# Sheet1.net
KiCad netlist of a schematic drawn in Altium Designer
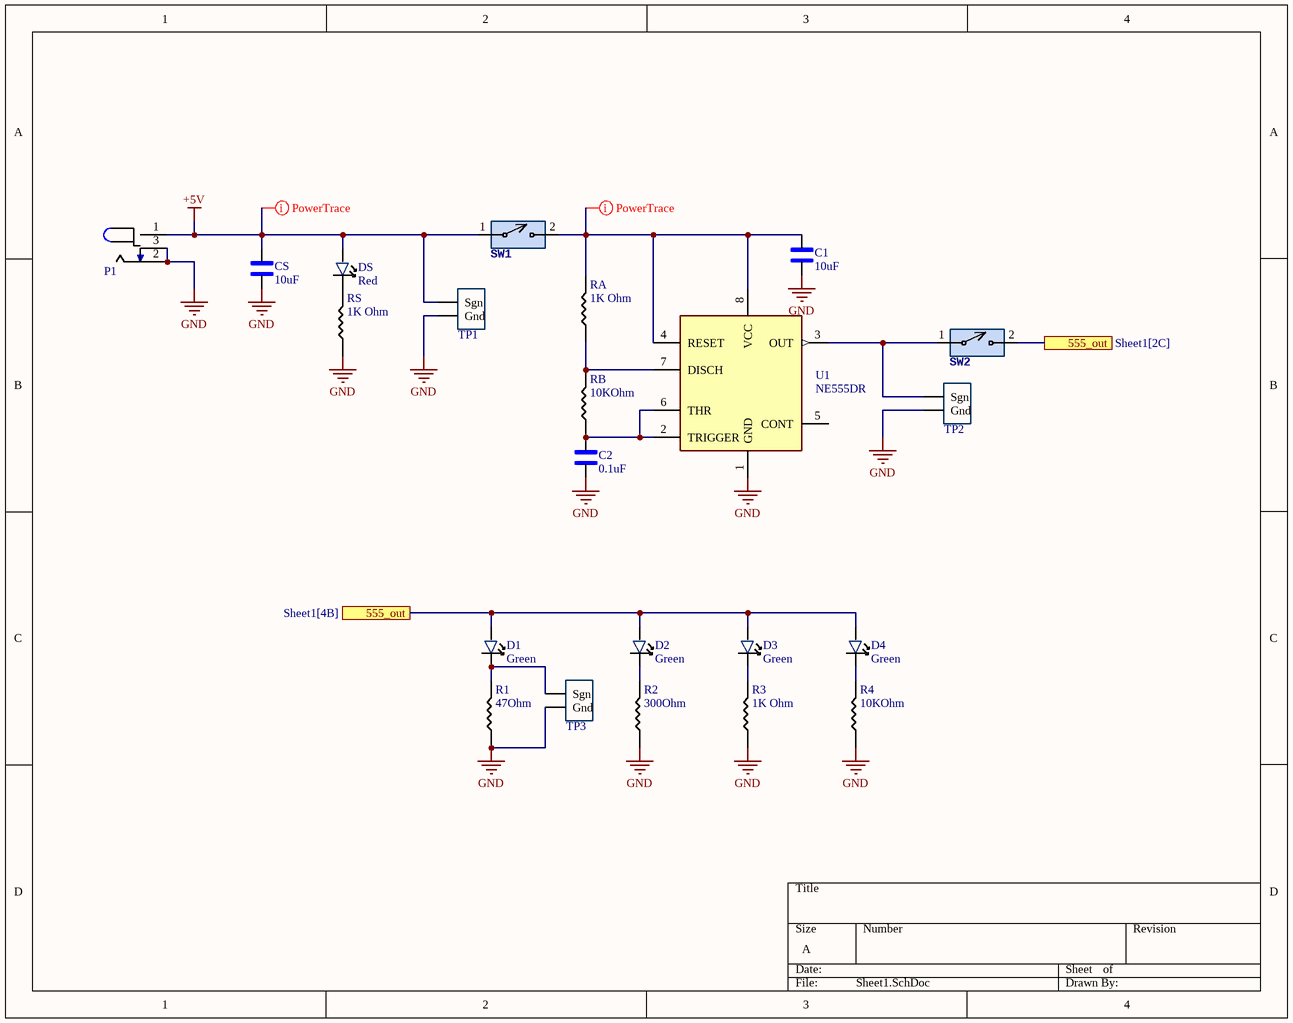
[diagram p0: Sheet1.SchDoc]

(export (version "E")
  (design (tool "Eeschema 10.0.6"))
  (components
    (comp (ref "C1")
      (value "10uF")
      (footprint "1206_Passive_Capacitor")
      (description "10uF ±10% 50V X5R 1206 Multilayer Ceramic Capacitors MLCC - SMD/SMT RoHS")
      (fields (field (name "LCSC PART#") "C13585") (field (name "MFR PART #") "CL31A106KBHNNNE"))
      (libsource (lib "ECEN5730Lib") (part "C_10uF_1206"))
    )
    (comp (ref "C2")
      (value "0.1uF")
      (footprint "1206_Passive_Capacitor")
      (description "MULTILAYER CERAMIC CAPACITORS MLCC - SMD/SMT 1UF 50V 1206 ROHS")
      (fields (field (name "MFR PART #") "CL31B105KBHNNNE") (field (name "LCSC PART#") "C1848"))
      (libsource (lib "ECEN5730Lib") (part "C_1uF_1206"))
    )
    (comp (ref "CS")
      (value "10uF")
      (footprint "1206_Passive_Capacitor")
      (description "10uF ±10% 50V X5R 1206 Multilayer Ceramic Capacitors MLCC - SMD/SMT RoHS")
      (fields (field (name "LCSC PART#") "C13585") (field (name "MFR PART #") "CL31A106KBHNNNE"))
      (libsource (lib "ECEN5730Lib") (part "C_10uF_1206"))
    )
    (comp (ref "D1")
      (value "Green")
      (footprint "LED_1206")
      (description "Green 513~528nm 1206 Light Emitting Diodes (LED) RoHS")
      (fields (field (name "MFR PART #") "SZYY1206G") (field (name "LCSC PART#") "C434439"))
      (libsource (lib "ECEN5730Lib") (part "LED_GREEN_1206"))
    )
    (comp (ref "D2")
      (value "Green")
      (footprint "LED_1206")
      (description "Green 513~528nm 1206 Light Emitting Diodes (LED) RoHS")
      (fields (field (name "MFR PART #") "SZYY1206G") (field (name "LCSC PART#") "C434439"))
      (libsource (lib "ECEN5730Lib") (part "LED_GREEN_1206"))
    )
    (comp (ref "D3")
      (value "Green")
      (footprint "LED_1206")
      (description "Green 513~528nm 1206 Light Emitting Diodes (LED) RoHS")
      (fields (field (name "MFR PART #") "SZYY1206G") (field (name "LCSC PART#") "C434439"))
      (libsource (lib "ECEN5730Lib") (part "LED_GREEN_1206"))
    )
    (comp (ref "D4")
      (value "Green")
      (footprint "LED_1206")
      (description "Green 513~528nm 1206 Light Emitting Diodes (LED) RoHS")
      (fields (field (name "MFR PART #") "SZYY1206G") (field (name "LCSC PART#") "C434439"))
      (libsource (lib "ECEN5730Lib") (part "LED_GREEN_1206"))
    )
    (comp (ref "DS")
      (value "Red")
      (footprint "LED_1206")
      (description "Red 621~631nm 1206 Light Emitting Diodes (LED) RoHS")
      (fields (field (name "MFR PART #") "15-21/R6C-FQ1R1B/2T") (field (name "LCSC PART#") "C93133"))
      (libsource (lib "ECEN5730Lib") (part "LED_RED_1206"))
    )
    (comp (ref "P1")
      (value "Power Jack")
      (footprint "Power_Jack")
      (description "Power Barrel Connector Jack 2.10mm ID (0.083\"), 5.50mm OD (0.217\") Through Hole, Right Angle")
      (fields (field (name "MFR PART #") "PJ-102A") (field (name "LCSC PART#") "C136744"))
      (libsource (lib "ECEN5730Lib") (part "P_Power Jack"))
    )
    (comp (ref "R1")
      (value "47Ohm")
      (footprint "1206_Passive_Resitor")
      (description "47Ω ±5% 0.25W ±200ppm/℃ 1206 Chip Resistor - Surface Mount RoHS")
      (fields (field (name "MFR PART #") "1206W4J0470T5E") (field (name "LCSC PART#") "C25384"))
      (libsource (lib "ECEN5730Lib") (part "R_47Ohm_1206"))
    )
    (comp (ref "R2")
      (value "300Ohm")
      (footprint "1206_Passive_Resitor")
      (description "CHIP RESISTOR - SURFACE MOUNT 300OHMS ±1% 1/4W 1206 ROHS")
      (fields (field (name "MFR PART #") "1206W4F3000T5E") (field (name "LCSC PART#") "C17887"))
      (libsource (lib "ECEN5730Lib") (part "R_300Ohm_1206"))
    )
    (comp (ref "R3")
      (value "1K Ohm")
      (footprint "1206_Passive_Resitor")
      (description "CHIP RESISTOR - SURFACE MOUNT 1KOHMS ±1% 1/4W 1206 ROHS")
      (fields (field (name "MFR PART #") "RNCP1206FTD1K00CT") (field (name "LCSC PART#") "C4410"))
      (libsource (lib "ECEN5730Lib") (part "R_1K_1206"))
    )
    (comp (ref "R4")
      (value "10KOhm")
      (footprint "1206_Passive_Resitor")
      (description "10 kOhms ±5% 0.25W, 1/4W Chip Resistor 1206 (3216 Metric) Automotive AEC-Q200 Thick Film")
      (fields (field (name "MFR PART #") "RMCF1206FT10K0") (field (name "LCSC PART#") "C17902"))
      (libsource (lib "ECEN5730Lib") (part "R_10KOhm_1206"))
    )
    (comp (ref "RA")
      (value "1K Ohm")
      (footprint "1206_Passive_Resitor")
      (description "CHIP RESISTOR - SURFACE MOUNT 1KOHMS ±1% 1/4W 1206 ROHS")
      (fields (field (name "MFR PART #") "RNCP1206FTD1K00CT") (field (name "LCSC PART#") "C4410"))
      (libsource (lib "ECEN5730Lib") (part "R_1K_1206"))
    )
    (comp (ref "RB")
      (value "10KOhm")
      (footprint "1206_Passive_Resitor")
      (description "10 kOhms ±5% 0.25W, 1/4W Chip Resistor 1206 (3216 Metric) Automotive AEC-Q200 Thick Film")
      (fields (field (name "MFR PART #") "RMCF1206FT10K0") (field (name "LCSC PART#") "C17902"))
      (libsource (lib "ECEN5730Lib") (part "R_10KOhm_1206"))
    )
    (comp (ref "RS")
      (value "1K Ohm")
      (footprint "1206_Passive_Resitor")
      (description "CHIP RESISTOR - SURFACE MOUNT 1KOHMS ±1% 1/4W 1206 ROHS")
      (fields (field (name "MFR PART #") "RNCP1206FTD1K00CT") (field (name "LCSC PART#") "C4410"))
      (libsource (lib "ECEN5730Lib") (part "R_1K_1206"))
    )
    (comp (ref "SW1")
      (value "SW_2Pin_100mil_Switch")
      (footprint "2Pin-Header-Conn")
      (description "2Pin Header")
      (fields (field (name "LCSC PART#") "C124375"))
      (libsource (lib "ECEN5730Lib") (part "SW_2Pin_100mil_Switch"))
    )
    (comp (ref "SW2")
      (value "SW_2Pin_100mil_Switch")
      (footprint "2Pin-Header-Conn")
      (description "2Pin Header")
      (fields (field (name "LCSC PART#") "C124375"))
      (libsource (lib "ECEN5730Lib") (part "SW_2Pin_100mil_Switch"))
    )
    (comp (ref "TP1")
      (value "10x Probe TP")
      (footprint "TP10x_Probe")
      (description "Test Point 300 mil centers")
      (libsource (lib "ECEN5730Lib") (part "TP_10x_Probe"))
    )
    (comp (ref "TP2")
      (value "10x Probe TP")
      (footprint "TP10x_Probe")
      (description "Test Point 300 mil centers")
      (libsource (lib "ECEN5730Lib") (part "TP_10x_Probe"))
    )
    (comp (ref "TP3")
      (value "10x Probe TP")
      (footprint "TP10x_Probe")
      (description "Test Point 300 mil centers")
      (libsource (lib "ECEN5730Lib") (part "TP_10x_Probe"))
    )
    (comp (ref "U1")
      (value "NE555DR")
      (footprint "TS555IDTTR")
      (description "555 Timer SOIC-8_150MIL ROHS 150ns Rise Time")
      (fields (field (name "LCSC PART#") "C7593"))
      (libsource (lib "ECEN5730Lib") (part "U_555_Slow"))
    )
  )
  (nets
    (net (code "1") (name "+5V") (class "Default")
      (node (ref "CS") (pin "2") (pinfunction "2_2") (pintype "passive"))
      (node (ref "DS") (pin "1") (pinfunction "1_1") (pintype "passive"))
      (node (ref "P1") (pin "1") (pinfunction "1_1") (pintype "power_in"))
      (node (ref "SW1") (pin "1") (pinfunction "1_1") (pintype "passive"))
      (node (ref "TP1") (pin "1") (pinfunction "Sgn_1") (pintype "passive"))
    )
    (net (code "2") (name "/555_out") (class "Default")
      (node (ref "D1") (pin "1") (pinfunction "1_1") (pintype "passive"))
      (node (ref "D2") (pin "1") (pinfunction "1_1") (pintype "passive"))
      (node (ref "D3") (pin "1") (pinfunction "1_1") (pintype "passive"))
      (node (ref "D4") (pin "1") (pinfunction "1_1") (pintype "passive"))
      (node (ref "SW2") (pin "2") (pinfunction "2_2") (pintype "passive"))
    )
    (net (code "3") (name "GND") (class "Default")
      (node (ref "C1") (pin "1") (pinfunction "1_1") (pintype "passive"))
      (node (ref "C2") (pin "2") (pinfunction "2_2") (pintype "passive"))
      (node (ref "CS") (pin "1") (pinfunction "1_1") (pintype "passive"))
      (node (ref "P1") (pin "2") (pinfunction "2_2") (pintype "power_in"))
      (node (ref "P1") (pin "3") (pinfunction "3_3") (pintype "power_in"))
      (node (ref "R1") (pin "1") (pinfunction "1_1") (pintype "passive"))
      (node (ref "R2") (pin "1") (pinfunction "1_1") (pintype "passive"))
      (node (ref "R3") (pin "1") (pinfunction "1_1") (pintype "passive"))
      (node (ref "R4") (pin "1") (pinfunction "1_1") (pintype "passive"))
      (node (ref "RS") (pin "1") (pinfunction "1_1") (pintype "passive"))
      (node (ref "TP1") (pin "2") (pinfunction "Gnd_2") (pintype "passive"))
      (node (ref "TP2") (pin "2") (pinfunction "Gnd_2") (pintype "passive"))
      (node (ref "TP3") (pin "2") (pinfunction "Gnd_2") (pintype "passive"))
      (node (ref "U1") (pin "1") (pinfunction "GND_1") (pintype "power_in"))
    )
    (net (code "4") (name "Net-(D2-Pad2)") (class "Default")
      (node (ref "D2") (pin "2") (pinfunction "2_2") (pintype "passive"))
      (node (ref "R2") (pin "2") (pinfunction "2_2") (pintype "passive"))
    )
    (net (code "5") (name "Net-(D3-Pad2)") (class "Default")
      (node (ref "D3") (pin "2") (pinfunction "2_2") (pintype "passive"))
      (node (ref "R3") (pin "2") (pinfunction "2_2") (pintype "passive"))
    )
    (net (code "6") (name "Net-(D4-Pad2)") (class "Default")
      (node (ref "D4") (pin "2") (pinfunction "2_2") (pintype "passive"))
      (node (ref "R4") (pin "2") (pinfunction "2_2") (pintype "passive"))
    )
    (net (code "7") (name "Net-(DS-Pad2)") (class "Default")
      (node (ref "DS") (pin "2") (pinfunction "2_2") (pintype "passive"))
      (node (ref "RS") (pin "2") (pinfunction "2_2") (pintype "passive"))
    )
    (net (code "8") (name "Net-(TP2-Sgn)") (class "Default")
      (node (ref "SW2") (pin "1") (pinfunction "1_1") (pintype "passive"))
      (node (ref "TP2") (pin "1") (pinfunction "Sgn_1") (pintype "passive"))
      (node (ref "U1") (pin "3") (pinfunction "OUT_3") (pintype "output"))
    )
    (net (code "9") (name "Net-(TP3-Sgn)") (class "Default")
      (node (ref "D1") (pin "2") (pinfunction "2_2") (pintype "passive"))
      (node (ref "R1") (pin "2") (pinfunction "2_2") (pintype "passive"))
      (node (ref "TP3") (pin "1") (pinfunction "Sgn_1") (pintype "passive"))
    )
    (net (code "10") (name "Net-(U1-DISCH)") (class "Default")
      (node (ref "RA") (pin "1") (pinfunction "1_1") (pintype "passive"))
      (node (ref "RB") (pin "2") (pinfunction "2_2") (pintype "passive"))
      (node (ref "U1") (pin "7") (pinfunction "DISCH_7") (pintype "passive"))
    )
    (net (code "11") (name "Net-(U1-RESET)") (class "Default")
      (node (ref "C1") (pin "2") (pinfunction "2_2") (pintype "passive"))
      (node (ref "RA") (pin "2") (pinfunction "2_2") (pintype "passive"))
      (node (ref "SW1") (pin "2") (pinfunction "2_2") (pintype "passive"))
      (node (ref "U1") (pin "4") (pinfunction "RESET_4") (pintype "passive"))
      (node (ref "U1") (pin "8") (pinfunction "VCC_8") (pintype "power_in"))
    )
    (net (code "12") (name "Net-(U1-THR)") (class "Default")
      (node (ref "C2") (pin "1") (pinfunction "1_1") (pintype "passive"))
      (node (ref "RB") (pin "1") (pinfunction "1_1") (pintype "passive"))
      (node (ref "U1") (pin "2") (pinfunction "TRIGGER_2") (pintype "passive"))
      (node (ref "U1") (pin "6") (pinfunction "THR_6") (pintype "passive"))
    )
    (net (code "13") (name "unconnected-(U1-CONT-Pad5)") (class "Default")
      (node (ref "U1") (pin "5") (pinfunction "CONT_5") (pintype "passive"))
    )
  )
)
